# unoshield-v2.net
KiCad netlist of a schematic drawn in EAGLE
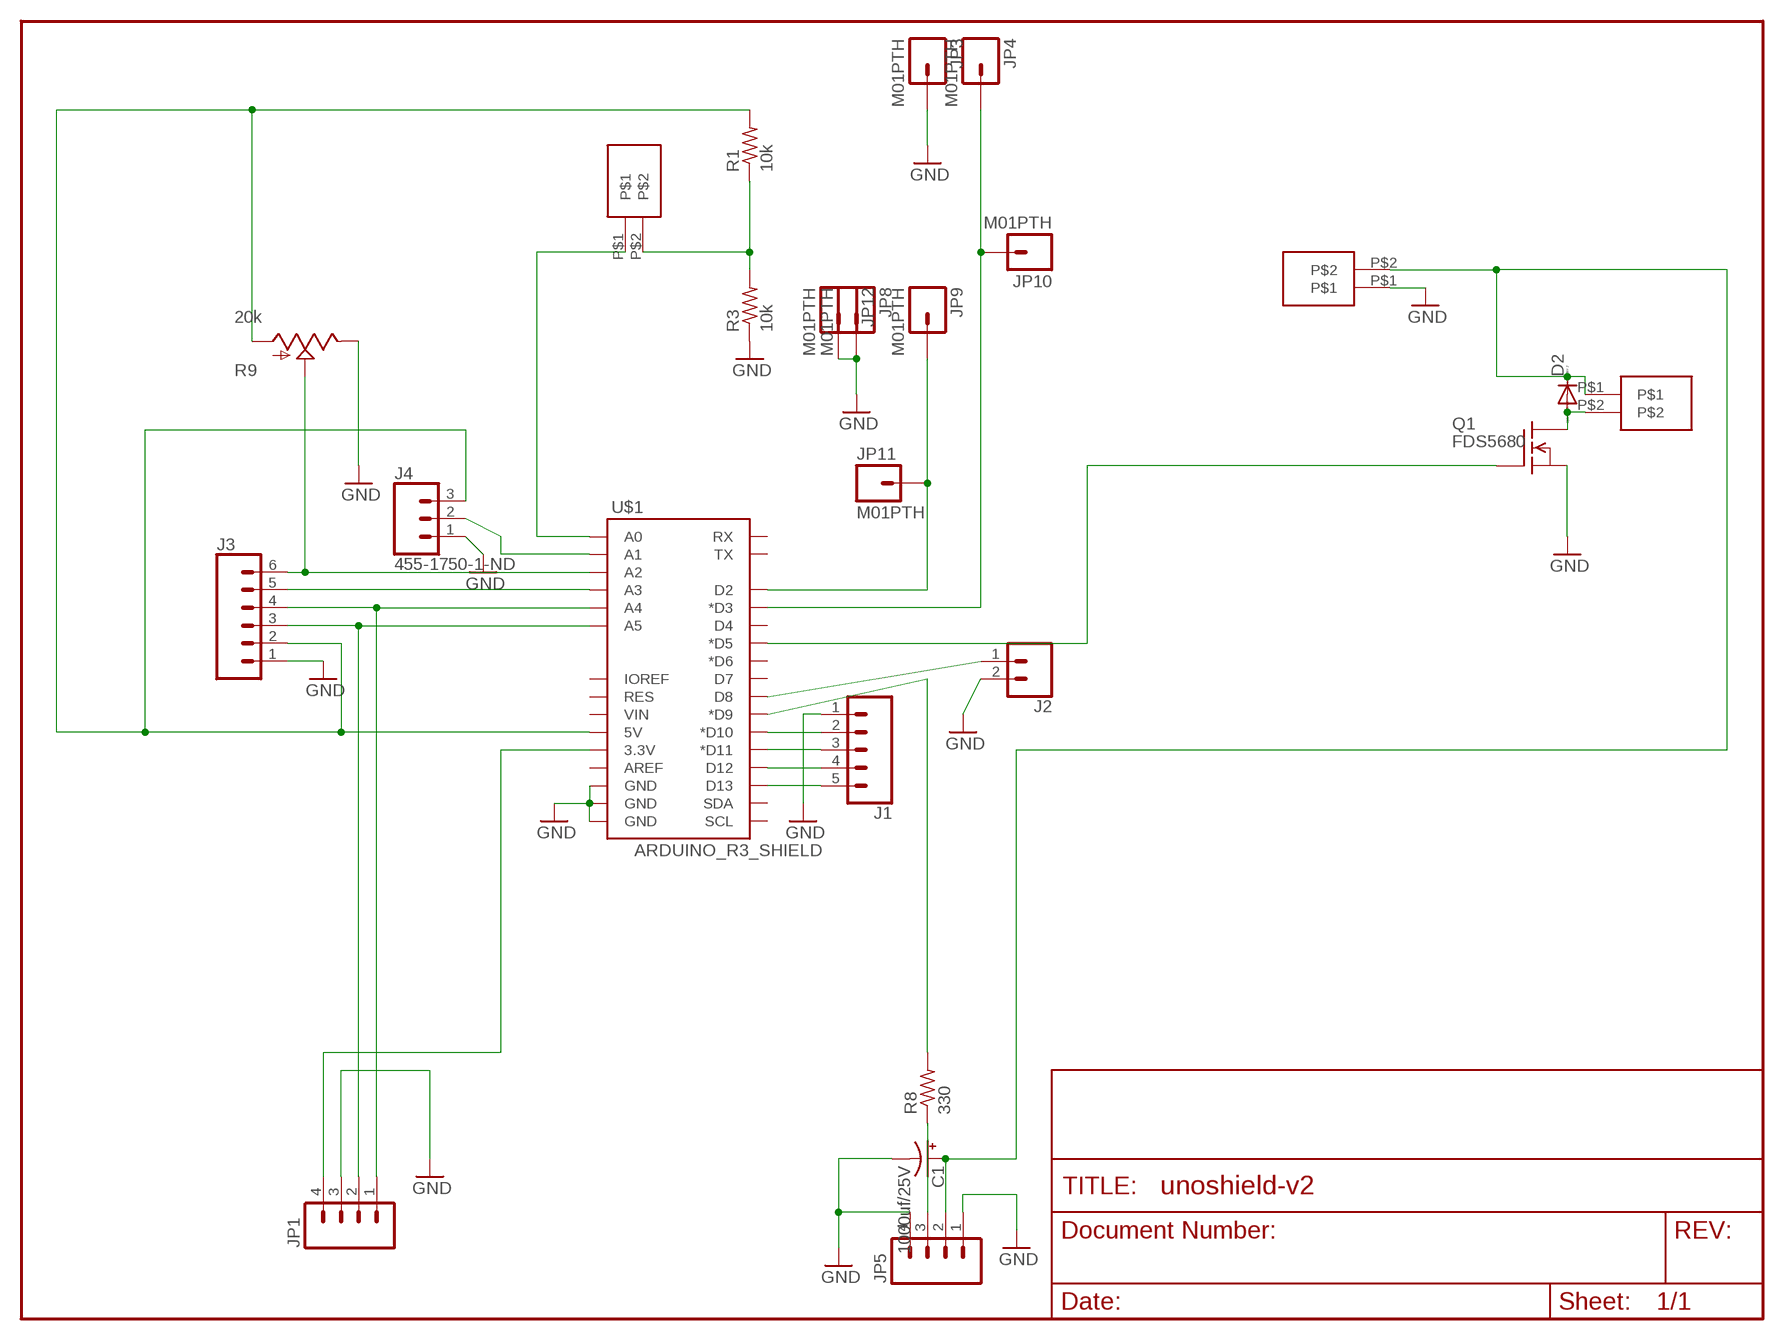
[diagram p0: schematic, sheet 1]

(export (version "E")
  (design (tool "Eeschema 10.0.6"))
  (components
    (comp (ref "C1")
      (value "1000uf/25V")
      (footprint "eagle-import:CPOL-RADIAL-1000UF-25V-KIT")
      (libsource (lib "eagle-import") (part "1000UF-25V(PTH)KIT"))
    )
    (comp (ref "D2")
      (value "DIODE-DO-214AC")
      (footprint "eagle-import:DO-214AC")
      (libsource (lib "eagle-import") (part "DIODE-DO-214AC"))
    )
    (comp (ref "J1")
      (value "CONN_05")
      (footprint "eagle-import:1X05")
      (libsource (lib "eagle-import") (part "CONN_05"))
    )
    (comp (ref "J2")
      (value "CONN_02")
      (footprint "eagle-import:1X02")
      (libsource (lib "eagle-import") (part "CONN_02"))
    )
    (comp (ref "J3")
      (value "CONN_06SILK_FEMALE_PTH")
      (footprint "eagle-import:1X06")
      (libsource (lib "eagle-import") (part "CONN_06SILK_FEMALE_PTH"))
    )
    (comp (ref "J4")
      (value "455-1750-1-ND")
      (footprint "eagle-import:1X03")
      (libsource (lib "eagle-import") (part "CONN_03"))
    )
    (comp (ref "JP1")
      (value "M04PTH")
      (footprint "eagle-import:1X04")
      (libsource (lib "eagle-import") (part "M04PTH"))
    )
    (comp (ref "JP3")
      (value "M01PTH")
      (footprint "eagle-import:1X01")
      (libsource (lib "eagle-import") (part "M01PTH"))
    )
    (comp (ref "JP4")
      (value "M01PTH")
      (footprint "eagle-import:1X01")
      (libsource (lib "eagle-import") (part "M01PTH"))
    )
    (comp (ref "JP5")
      (value "M04PTH")
      (footprint "eagle-import:1X04")
      (libsource (lib "eagle-import") (part "M04PTH"))
    )
    (comp (ref "JP8")
      (value "M01PTH")
      (footprint "eagle-import:1X01")
      (libsource (lib "eagle-import") (part "M01PTH"))
    )
    (comp (ref "JP9")
      (value "M01PTH")
      (footprint "eagle-import:1X01")
      (libsource (lib "eagle-import") (part "M01PTH"))
    )
    (comp (ref "JP10")
      (value "M01PTH")
      (footprint "eagle-import:1X01")
      (libsource (lib "eagle-import") (part "M01PTH"))
    )
    (comp (ref "JP11")
      (value "M01PTH")
      (footprint "eagle-import:1X01")
      (libsource (lib "eagle-import") (part "M01PTH"))
    )
    (comp (ref "JP12")
      (value "M01PTH")
      (footprint "eagle-import:1X01")
      (libsource (lib "eagle-import") (part "M01PTH"))
    )
    (comp (ref "Q1")
      (value "FDS5680")
      (footprint "eagle-import:SO-8")
      (libsource (lib "eagle-import") (part "FDS5680"))
    )
    (comp (ref "R1")
      (value "10k")
      (footprint "eagle-import:R0603")
      (libsource (lib "eagle-import") (part "R-US_R0603"))
    )
    (comp (ref "R3")
      (value "10k")
      (footprint "eagle-import:R0603")
      (libsource (lib "eagle-import") (part "R-US_R0603"))
    )
    (comp (ref "R8")
      (value "330")
      (footprint "eagle-import:R0603")
      (libsource (lib "eagle-import") (part "R-US_R0603"))
    )
    (comp (ref "R9")
      (value "20k")
      (footprint "eagle-import:ALPS_POT_KIT")
      (libsource (lib "eagle-import") (part "POTALPS-KIT"))
    )
    (comp (ref "U$1")
      (value "ARDUINO_R3_SHIELD")
      (footprint "eagle-import:UNO_R3_SHIELD")
      (libsource (lib "eagle-import") (part "ARDUINO_R3_SHIELD"))
    )
    (comp (ref "U$6")
      (value "SPRING-TERMINAL")
      (footprint "eagle-import:SPRING-TERMINAL")
      (libsource (lib "eagle-import") (part "SPRING-TERMINAL"))
    )
    (comp (ref "X1")
      (value "SPRING-TERMINAL")
      (footprint "eagle-import:SPRING-TERMINAL")
      (libsource (lib "eagle-import") (part "SPRING-TERMINAL"))
    )
    (comp (ref "X2")
      (value "SPRING-TERMINAL")
      (footprint "eagle-import:SPRING-TERMINAL")
      (libsource (lib "eagle-import") (part "SPRING-TERMINAL"))
    )
  )
  (nets
    (net (code "1") (name "GND") (class "Default")
      (node (ref "C1") (pin "-") (pinfunction "-_-") (pintype "passive"))
      (node (ref "J1") (pin "1") (pinfunction "1_1") (pintype "passive"))
      (node (ref "J2") (pin "2") (pinfunction "2_2") (pintype "passive"))
      (node (ref "J3") (pin "1") (pinfunction "1_1") (pintype "passive"))
      (node (ref "J4") (pin "1") (pinfunction "1_1") (pintype "passive"))
      (node (ref "JP1") (pin "3") (pinfunction "3_3") (pintype "passive"))
      (node (ref "JP12") (pin "1") (pinfunction "1_1") (pintype "passive"))
      (node (ref "JP3") (pin "1") (pinfunction "1_1") (pintype "passive"))
      (node (ref "JP5") (pin "1") (pinfunction "1_1") (pintype "passive"))
      (node (ref "JP5") (pin "4") (pinfunction "4_4") (pintype "passive"))
      (node (ref "JP8") (pin "1") (pinfunction "1_1") (pintype "passive"))
      (node (ref "Q1") (pin "1") (pinfunction "S_1") (pintype "passive"))
      (node (ref "Q1") (pin "2") (pinfunction "S_2") (pintype "passive"))
      (node (ref "Q1") (pin "3") (pinfunction "S_3") (pintype "passive"))
      (node (ref "R3") (pin "1") (pinfunction "1_1") (pintype "passive"))
      (node (ref "R9") (pin "P$1") (pinfunction "E_P$1") (pintype "passive"))
      (node (ref "U$1") (pin "GND@0") (pinfunction "GND_GND@0") (pintype "bidirectional"))
      (node (ref "U$1") (pin "GND@1") (pinfunction "GND_GND@1") (pintype "bidirectional"))
      (node (ref "U$1") (pin "GND@2") (pinfunction "GND_GND@2") (pintype "bidirectional"))
      (node (ref "X1") (pin "P$1") (pinfunction "P$1_P$1") (pintype "bidirectional"))
    )
    (net (code "2") (name "Net-(C1-Pad+)") (class "Default")
      (node (ref "C1") (pin "+") (pinfunction "+_+") (pintype "passive"))
      (node (ref "D2") (pin "C") (pinfunction "C_C") (pintype "passive"))
      (node (ref "JP5") (pin "2") (pinfunction "2_2") (pintype "passive"))
      (node (ref "U$6") (pin "P$1") (pinfunction "P$1_P$1") (pintype "bidirectional"))
      (node (ref "X1") (pin "P$2") (pinfunction "P$2_P$2") (pintype "bidirectional"))
    )
    (net (code "3") (name "Net-(D2-PadA)") (class "Default")
      (node (ref "D2") (pin "A") (pinfunction "A_A") (pintype "passive"))
      (node (ref "Q1") (pin "5") (pinfunction "D_5") (pintype "passive"))
      (node (ref "Q1") (pin "6") (pinfunction "D_6") (pintype "passive"))
      (node (ref "Q1") (pin "7") (pinfunction "D_7") (pintype "passive"))
      (node (ref "Q1") (pin "8") (pinfunction "D_8") (pintype "passive"))
      (node (ref "U$6") (pin "P$2") (pinfunction "P$2_P$2") (pintype "bidirectional"))
    )
    (net (code "4") (name "Net-(J1-Pad4)") (class "Default")
      (node (ref "J1") (pin "4") (pinfunction "4_4") (pintype "passive"))
      (node (ref "U$1") (pin "D12") (pinfunction "D12_D12") (pintype "bidirectional"))
    )
    (net (code "5") (name "Net-(J1-Pad5)") (class "Default")
      (node (ref "J1") (pin "5") (pinfunction "5_5") (pintype "passive"))
      (node (ref "U$1") (pin "D13") (pinfunction "D13_D13") (pintype "bidirectional"))
    )
    (net (code "6") (name "Net-(J2-Pad1)") (class "Default")
      (node (ref "J2") (pin "1") (pinfunction "1_1") (pintype "passive"))
      (node (ref "U$1") (pin "D8") (pinfunction "D8_D8") (pintype "bidirectional"))
    )
    (net (code "7") (name "Net-(J3-Pad3)") (class "Default")
      (node (ref "J3") (pin "3") (pinfunction "3_3") (pintype "passive"))
      (node (ref "JP1") (pin "2") (pinfunction "2_2") (pintype "passive"))
      (node (ref "U$1") (pin "A5") (pinfunction "A5_A5") (pintype "bidirectional"))
    )
    (net (code "8") (name "Net-(J3-Pad4)") (class "Default")
      (node (ref "J3") (pin "4") (pinfunction "4_4") (pintype "passive"))
      (node (ref "JP1") (pin "1") (pinfunction "1_1") (pintype "passive"))
      (node (ref "U$1") (pin "A4") (pinfunction "A4_A4") (pintype "bidirectional"))
    )
    (net (code "9") (name "Net-(J3-Pad5)") (class "Default")
      (node (ref "J3") (pin "5") (pinfunction "5_5") (pintype "passive"))
      (node (ref "U$1") (pin "A3") (pinfunction "A3_A3") (pintype "bidirectional"))
    )
    (net (code "10") (name "Net-(J4-Pad2)") (class "Default")
      (node (ref "J4") (pin "2") (pinfunction "2_2") (pintype "passive"))
      (node (ref "U$1") (pin "A1") (pinfunction "A1_A1") (pintype "bidirectional"))
    )
    (net (code "11") (name "Net-(JP1-Pad4)") (class "Default")
      (node (ref "JP1") (pin "4") (pinfunction "4_4") (pintype "passive"))
      (node (ref "U$1") (pin "3.3V") (pinfunction "3.3V_3.3V") (pintype "bidirectional"))
    )
    (net (code "12") (name "Net-(JP5-Pad3)") (class "Default")
      (node (ref "JP5") (pin "3") (pinfunction "3_3") (pintype "passive"))
      (node (ref "R8") (pin "1") (pinfunction "1_1") (pintype "passive"))
    )
    (net (code "13") (name "Net-(JP11-Pad1)") (class "Default")
      (node (ref "JP11") (pin "1") (pinfunction "1_1") (pintype "passive"))
      (node (ref "JP9") (pin "1") (pinfunction "1_1") (pintype "passive"))
      (node (ref "U$1") (pin "D2") (pinfunction "D2_D2") (pintype "bidirectional"))
    )
    (net (code "14") (name "Net-(Q1-G)") (class "Default")
      (node (ref "Q1") (pin "4") (pinfunction "G_4") (pintype "passive"))
      (node (ref "U$1") (pin "D5") (pinfunction "*D5_D5") (pintype "bidirectional"))
    )
    (net (code "15") (name "Net-(R1-Pad1)") (class "Default")
      (node (ref "R1") (pin "1") (pinfunction "1_1") (pintype "passive"))
      (node (ref "R3") (pin "2") (pinfunction "2_2") (pintype "passive"))
      (node (ref "X2") (pin "P$2") (pinfunction "P$2_P$2") (pintype "bidirectional"))
    )
    (net (code "16") (name "Net-(R9-A)") (class "Default")
      (node (ref "J3") (pin "2") (pinfunction "2_2") (pintype "passive"))
      (node (ref "J4") (pin "3") (pinfunction "3_3") (pintype "passive"))
      (node (ref "R1") (pin "2") (pinfunction "2_2") (pintype "passive"))
      (node (ref "R9") (pin "P$3") (pinfunction "A_P$3") (pintype "passive"))
      (node (ref "U$1") (pin "5V") (pinfunction "5V_5V") (pintype "bidirectional"))
    )
    (net (code "17") (name "Net-(R9-S)") (class "Default")
      (node (ref "J3") (pin "6") (pinfunction "6_6") (pintype "passive"))
      (node (ref "R9") (pin "P$2") (pinfunction "S_P$2") (pintype "passive"))
      (node (ref "U$1") (pin "A2") (pinfunction "A2_A2") (pintype "bidirectional"))
    )
    (net (code "18") (name "Net-(U$1-*D3)") (class "Default")
      (node (ref "JP10") (pin "1") (pinfunction "1_1") (pintype "passive"))
      (node (ref "JP4") (pin "1") (pinfunction "1_1") (pintype "passive"))
      (node (ref "U$1") (pin "D3") (pinfunction "*D3_D3") (pintype "bidirectional"))
    )
    (net (code "19") (name "Net-(U$1-*D9)") (class "Default")
      (node (ref "R8") (pin "2") (pinfunction "2_2") (pintype "passive"))
      (node (ref "U$1") (pin "D9") (pinfunction "*D9_D9") (pintype "bidirectional"))
    )
    (net (code "20") (name "Net-(U$1-*D10)") (class "Default")
      (node (ref "J1") (pin "2") (pinfunction "2_2") (pintype "passive"))
      (node (ref "U$1") (pin "D10") (pinfunction "*D10_D10") (pintype "bidirectional"))
    )
    (net (code "21") (name "Net-(U$1-*D11)") (class "Default")
      (node (ref "J1") (pin "3") (pinfunction "3_3") (pintype "passive"))
      (node (ref "U$1") (pin "D11") (pinfunction "*D11_D11") (pintype "bidirectional"))
    )
    (net (code "22") (name "Net-(U$1-PadA0)") (class "Default")
      (node (ref "U$1") (pin "A0") (pinfunction "A0_A0") (pintype "bidirectional"))
      (node (ref "X2") (pin "P$1") (pinfunction "P$1_P$1") (pintype "bidirectional"))
    )
    (net (code "23") (name "unconnected-(U$1-*D6-PadD6)") (class "Default")
      (node (ref "U$1") (pin "D6") (pinfunction "*D6_D6") (pintype "bidirectional"))
    )
    (net (code "24") (name "unconnected-(U$1-PadAREF)") (class "Default")
      (node (ref "U$1") (pin "AREF") (pinfunction "AREF_AREF") (pintype "bidirectional"))
    )
    (net (code "25") (name "unconnected-(U$1-PadD4)") (class "Default")
      (node (ref "U$1") (pin "D4") (pinfunction "D4_D4") (pintype "bidirectional"))
    )
    (net (code "26") (name "unconnected-(U$1-PadD7)") (class "Default")
      (node (ref "U$1") (pin "D7") (pinfunction "D7_D7") (pintype "bidirectional"))
    )
    (net (code "27") (name "unconnected-(U$1-PadIOREF)") (class "Default")
      (node (ref "U$1") (pin "IOREF") (pinfunction "IOREF_IOREF") (pintype "bidirectional"))
    )
    (net (code "28") (name "unconnected-(U$1-PadRES)") (class "Default")
      (node (ref "U$1") (pin "RES") (pinfunction "RES_RES") (pintype "bidirectional"))
    )
    (net (code "29") (name "unconnected-(U$1-PadRX)") (class "Default")
      (node (ref "U$1") (pin "RX") (pinfunction "RX_RX") (pintype "bidirectional"))
    )
    (net (code "30") (name "unconnected-(U$1-PadSCL)") (class "Default")
      (node (ref "U$1") (pin "SCL") (pinfunction "SCL_SCL") (pintype "bidirectional"))
    )
    (net (code "31") (name "unconnected-(U$1-PadSDA)") (class "Default")
      (node (ref "U$1") (pin "SDA") (pinfunction "SDA_SDA") (pintype "bidirectional"))
    )
    (net (code "32") (name "unconnected-(U$1-PadTX)") (class "Default")
      (node (ref "U$1") (pin "TX") (pinfunction "TX_TX") (pintype "bidirectional"))
    )
    (net (code "33") (name "unconnected-(U$1-PadVIN)") (class "Default")
      (node (ref "U$1") (pin "VIN") (pinfunction "VIN_VIN") (pintype "bidirectional"))
    )
  )
)
